# Sensor.net
KiCad netlist of a schematic drawn in Altium Designer
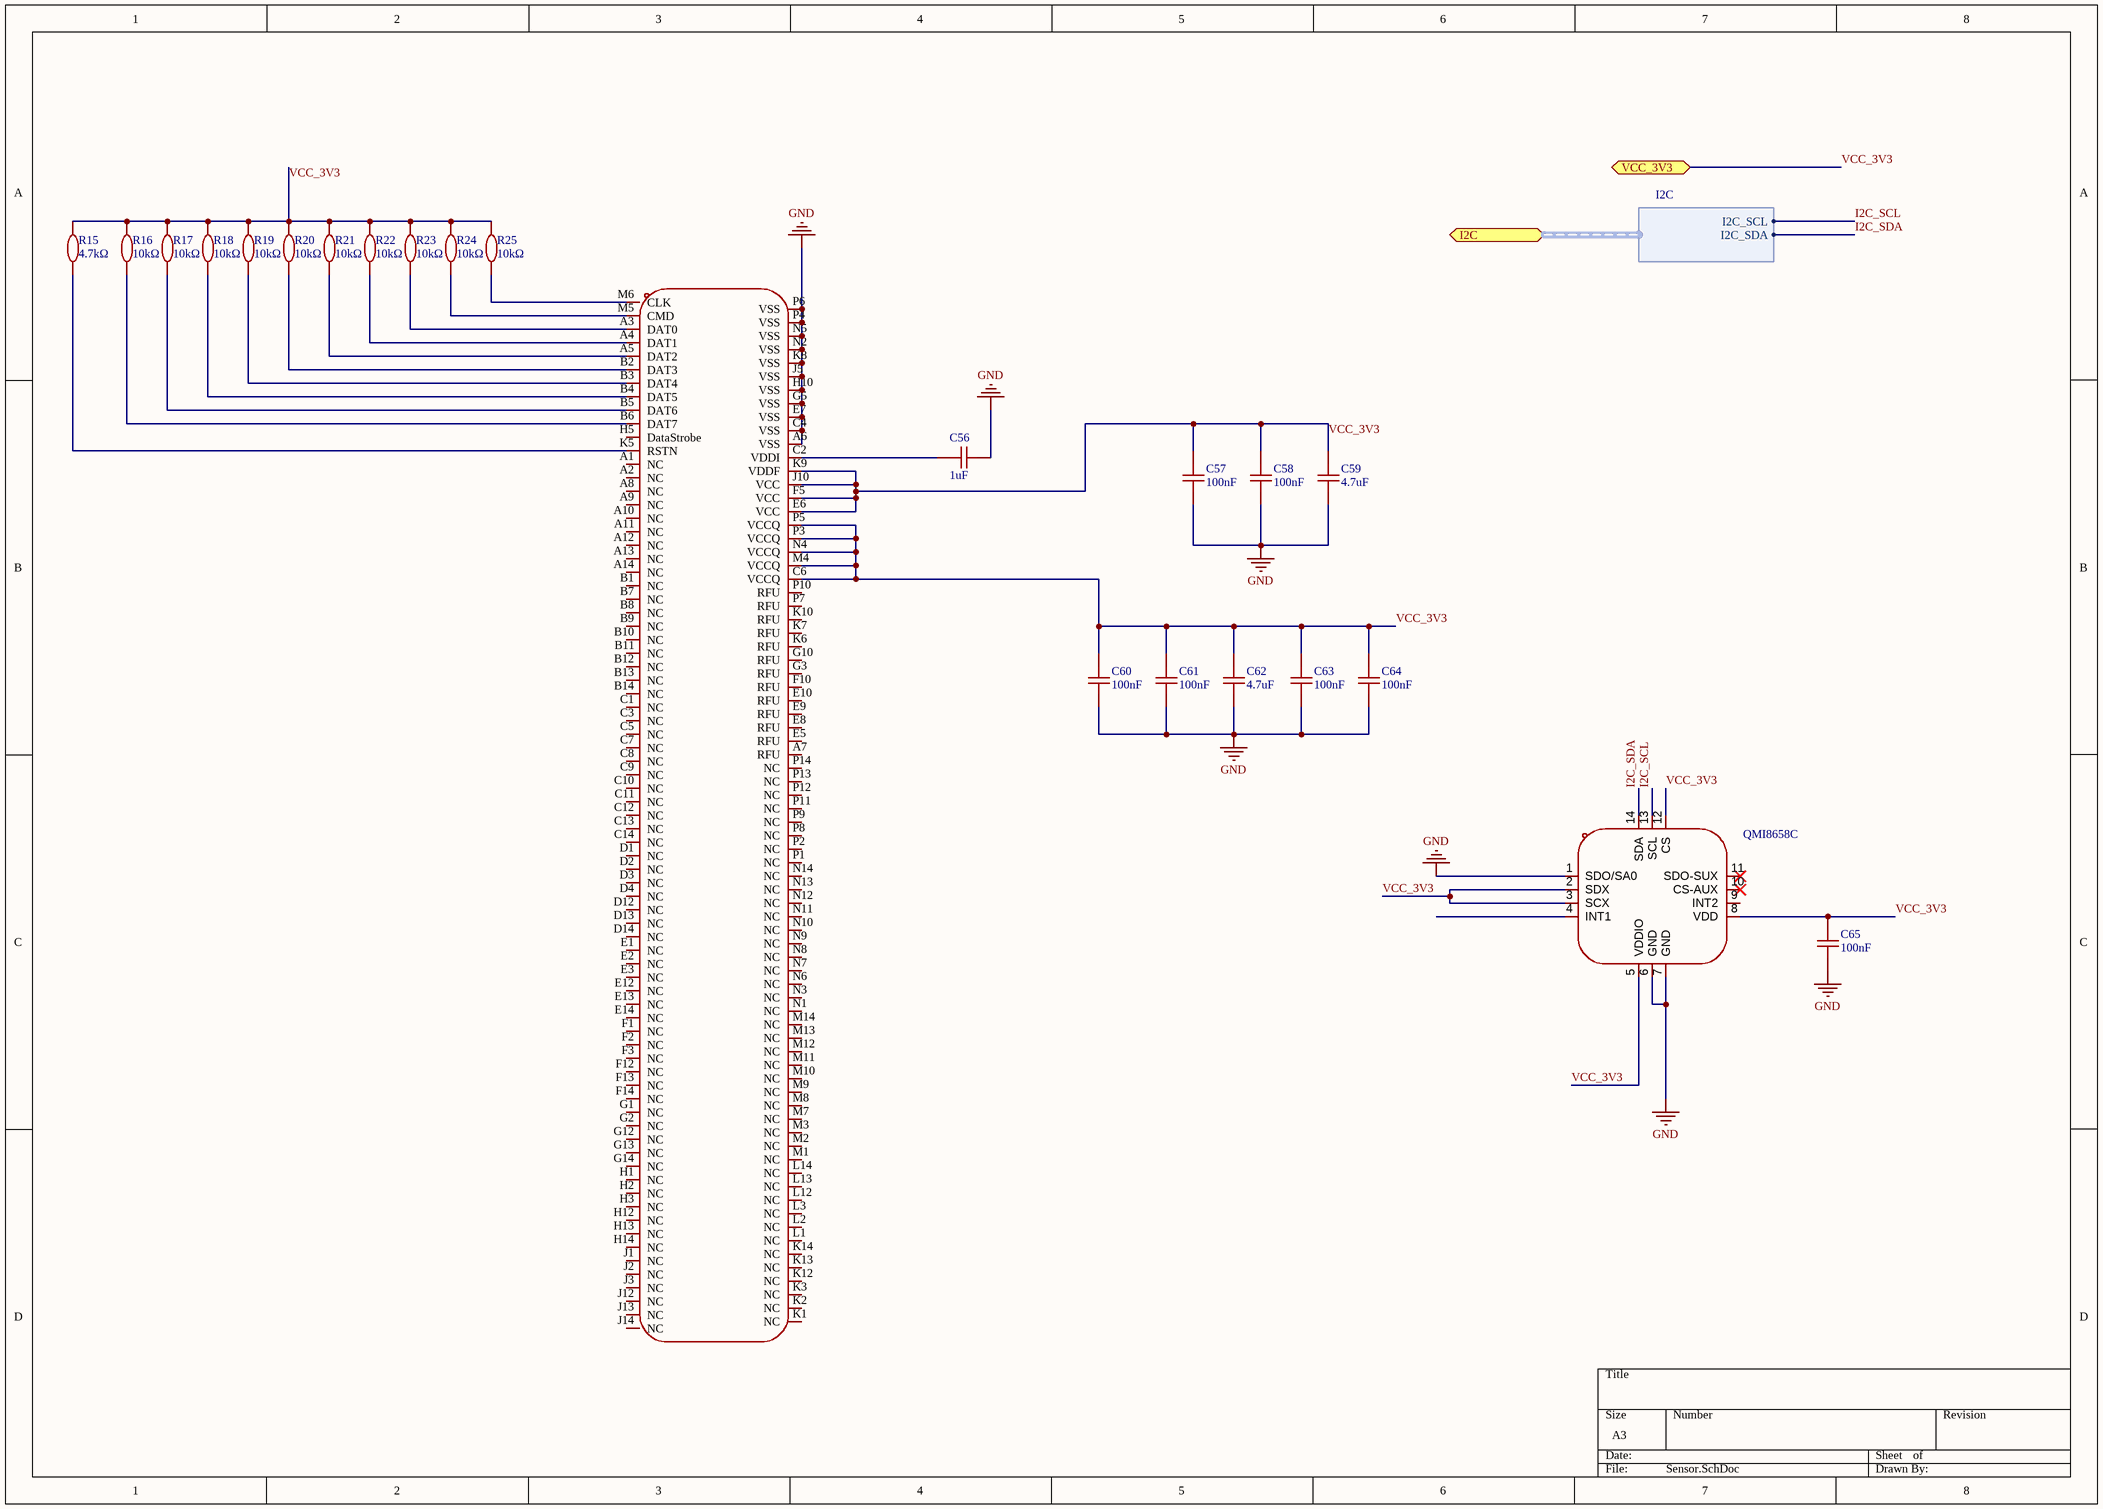
[diagram p0: Sensor.SchDoc]

(export (version "E")
  (design (tool "Eeschema 10.0.6"))
  (components
    (comp (ref "C56")
      (value "1uF")
      (footprint "C0402")
      (description "50V 1uF X5R ±10% 0402 Ceramic Capacitors ROHS")
      (libsource (lib "RLC") (part "1uF"))
    )
    (comp (ref "C57")
      (value "100nF")
      (footprint "C0402")
      (description "50V 100nF X7R ±10% 0402 Ceramic Capacitors ROHS")
      (libsource (lib "RLC") (part "100nF"))
    )
    (comp (ref "C58")
      (value "100nF")
      (footprint "C0402")
      (description "50V 100nF X7R ±10% 0402 Ceramic Capacitors ROHS")
      (libsource (lib "RLC") (part "100nF"))
    )
    (comp (ref "C59")
      (value "4.7uF")
      (footprint "C0402")
      (description "10V 4.7uF X5R ±20% 0402 Ceramic Capacitors ROHS")
      (libsource (lib "RLC") (part "4.7uF"))
    )
    (comp (ref "C60")
      (value "100nF")
      (footprint "C0402")
      (description "50V 100nF X7R ±10% 0402 Ceramic Capacitors ROHS")
      (libsource (lib "RLC") (part "100nF"))
    )
    (comp (ref "C61")
      (value "100nF")
      (footprint "C0402")
      (description "50V 100nF X7R ±10% 0402 Ceramic Capacitors ROHS")
      (libsource (lib "RLC") (part "100nF"))
    )
    (comp (ref "C62")
      (value "4.7uF")
      (footprint "C0402")
      (description "10V 4.7uF X5R ±20% 0402 Ceramic Capacitors ROHS")
      (libsource (lib "RLC") (part "4.7uF"))
    )
    (comp (ref "C63")
      (value "100nF")
      (footprint "C0402")
      (description "50V 100nF X7R ±10% 0402 Ceramic Capacitors ROHS")
      (libsource (lib "RLC") (part "100nF"))
    )
    (comp (ref "C64")
      (value "100nF")
      (footprint "C0402")
      (description "50V 100nF X7R ±10% 0402 Ceramic Capacitors ROHS")
      (libsource (lib "RLC") (part "100nF"))
    )
    (comp (ref "C65")
      (value "100nF")
      (footprint "C0402")
      (description "50V 100nF X7R ±10% 0402 Ceramic Capacitors ROHS")
      (libsource (lib "RLC") (part "100nF"))
    )
    (comp (ref "R15")
      (value "4.7kΩ")
      (footprint "R0402")
      (description "62.5mW 10kΩ 50V ±100ppm/℃ Thick Film Resistor ±1% 0402 Chip Resistor - Surface Mount ROHS")
      (libsource (lib "RLC") (part "10kΩ"))
    )
    (comp (ref "R16")
      (value "10kΩ")
      (footprint "R0402")
      (description "62.5mW 10kΩ 50V ±100ppm/℃ Thick Film Resistor ±1% 0402 Chip Resistor - Surface Mount ROHS")
      (libsource (lib "RLC") (part "10kΩ"))
    )
    (comp (ref "R17")
      (value "10kΩ")
      (footprint "R0402")
      (description "62.5mW 10kΩ 50V ±100ppm/℃ Thick Film Resistor ±1% 0402 Chip Resistor - Surface Mount ROHS")
      (libsource (lib "RLC") (part "10kΩ"))
    )
    (comp (ref "R18")
      (value "10kΩ")
      (footprint "R0402")
      (description "62.5mW 10kΩ 50V ±100ppm/℃ Thick Film Resistor ±1% 0402 Chip Resistor - Surface Mount ROHS")
      (libsource (lib "RLC") (part "10kΩ"))
    )
    (comp (ref "R19")
      (value "10kΩ")
      (footprint "R0402")
      (description "62.5mW 10kΩ 50V ±100ppm/℃ Thick Film Resistor ±1% 0402 Chip Resistor - Surface Mount ROHS")
      (libsource (lib "RLC") (part "10kΩ"))
    )
    (comp (ref "R20")
      (value "10kΩ")
      (footprint "R0402")
      (description "62.5mW 10kΩ 50V ±100ppm/℃ Thick Film Resistor ±1% 0402 Chip Resistor - Surface Mount ROHS")
      (libsource (lib "RLC") (part "10kΩ"))
    )
    (comp (ref "R21")
      (value "10kΩ")
      (footprint "R0402")
      (description "62.5mW 10kΩ 50V ±100ppm/℃ Thick Film Resistor ±1% 0402 Chip Resistor - Surface Mount ROHS")
      (libsource (lib "RLC") (part "10kΩ"))
    )
    (comp (ref "R22")
      (value "10kΩ")
      (footprint "R0402")
      (description "62.5mW 10kΩ 50V ±100ppm/℃ Thick Film Resistor ±1% 0402 Chip Resistor - Surface Mount ROHS")
      (libsource (lib "RLC") (part "10kΩ"))
    )
    (comp (ref "R23")
      (value "10kΩ")
      (footprint "R0402")
      (description "62.5mW 10kΩ 50V ±100ppm/℃ Thick Film Resistor ±1% 0402 Chip Resistor - Surface Mount ROHS")
      (libsource (lib "RLC") (part "10kΩ"))
    )
    (comp (ref "R24")
      (value "10kΩ")
      (footprint "R0402")
      (description "62.5mW 10kΩ 50V ±100ppm/℃ Thick Film Resistor ±1% 0402 Chip Resistor - Surface Mount ROHS")
      (libsource (lib "RLC") (part "10kΩ"))
    )
    (comp (ref "R25")
      (value "10kΩ")
      (footprint "R0402")
      (description "62.5mW 10kΩ 50V ±100ppm/℃ Thick Film Resistor ±1% 0402 Chip Resistor - Surface Mount ROHS")
      (libsource (lib "RLC") (part "10kΩ"))
    )
    (comp (ref "U10")
      (value "QMI8658C")
      (footprint "LGA-14_L3.0-W2.5-P0.50-BR")
      (description "低噪声、宽带宽6D惯性测量单元，带运动协处理器和传感器融合功能")
      (libsource (lib "IC") (part "QMI8658C"))
    )
    (comp (ref "U11")
      (value "KLM8G1GETF-B041")
      (footprint "FBGA-153_L13.0-W11.5-P0.50_KLMAG1JETD-B041")
      (description "8GB 2.7V~3.6V eMMC 5.1 330/50 MB/s FBGA-153(11.5x13) Memory (ICs) ROHS")
      (fields (field (name "MANUFACTURER") "SAMSUNG(三星半导体)"))
      (libsource (lib "IC") (part "KLM8G1GETF-B041_1"))
    )
  )
  (nets
    (net (code "2") (name "/I2C_SCL") (class "Default")
      (node (ref "U10") (pin "13") (pinfunction "SCL_13") (pintype "passive"))
    )
    (net (code "3") (name "/I2C_SDA") (class "Default")
      (node (ref "U10") (pin "14") (pinfunction "SDA_14") (pintype "passive"))
    )
    (net (code "4") (name "/VCC_3V3") (class "Default")
      (node (ref "C57") (pin "2") (pinfunction "2_2") (pintype "passive"))
      (node (ref "C58") (pin "2") (pinfunction "2_2") (pintype "passive"))
      (node (ref "C59") (pin "2") (pinfunction "2_2") (pintype "passive"))
      (node (ref "C60") (pin "2") (pinfunction "2_2") (pintype "passive"))
      (node (ref "C61") (pin "2") (pinfunction "2_2") (pintype "passive"))
      (node (ref "C62") (pin "2") (pinfunction "2_2") (pintype "passive"))
      (node (ref "C63") (pin "2") (pinfunction "2_2") (pintype "passive"))
      (node (ref "C64") (pin "2") (pinfunction "2_2") (pintype "passive"))
      (node (ref "C65") (pin "2") (pinfunction "2_2") (pintype "passive"))
      (node (ref "R15") (pin "2") (pinfunction "2_2") (pintype "passive"))
      (node (ref "R16") (pin "2") (pinfunction "2_2") (pintype "passive"))
      (node (ref "R17") (pin "2") (pinfunction "2_2") (pintype "passive"))
      (node (ref "R18") (pin "2") (pinfunction "2_2") (pintype "passive"))
      (node (ref "R19") (pin "2") (pinfunction "2_2") (pintype "passive"))
      (node (ref "R20") (pin "2") (pinfunction "2_2") (pintype "passive"))
      (node (ref "R21") (pin "2") (pinfunction "2_2") (pintype "passive"))
      (node (ref "R22") (pin "2") (pinfunction "2_2") (pintype "passive"))
      (node (ref "R23") (pin "2") (pinfunction "2_2") (pintype "passive"))
      (node (ref "R24") (pin "2") (pinfunction "2_2") (pintype "passive"))
      (node (ref "R25") (pin "2") (pinfunction "2_2") (pintype "passive"))
      (node (ref "U10") (pin "12") (pinfunction "CS_12") (pintype "passive"))
      (node (ref "U10") (pin "2") (pinfunction "SDX_2") (pintype "passive"))
      (node (ref "U10") (pin "3") (pinfunction "SCX_3") (pintype "passive"))
      (node (ref "U10") (pin "5") (pinfunction "VDDIO_5") (pintype "passive"))
      (node (ref "U10") (pin "8") (pinfunction "VDD_8") (pintype "passive"))
      (node (ref "U11") (pin "C6") (pinfunction "VCCQ_C6") (pintype "passive"))
      (node (ref "U11") (pin "E6") (pinfunction "VCC_E6") (pintype "passive"))
      (node (ref "U11") (pin "F5") (pinfunction "VCC_F5") (pintype "passive"))
      (node (ref "U11") (pin "J10") (pinfunction "VCC_J10") (pintype "passive"))
      (node (ref "U11") (pin "K9") (pinfunction "VDDF_K9") (pintype "passive"))
      (node (ref "U11") (pin "M4") (pinfunction "VCCQ_M4") (pintype "passive"))
      (node (ref "U11") (pin "N4") (pinfunction "VCCQ_N4") (pintype "passive"))
      (node (ref "U11") (pin "P3") (pinfunction "VCCQ_P3") (pintype "passive"))
      (node (ref "U11") (pin "P5") (pinfunction "VCCQ_P5") (pintype "passive"))
    )
    (net (code "6") (name "GND") (class "Default")
      (node (ref "C56") (pin "2") (pinfunction "2_2") (pintype "passive"))
      (node (ref "C57") (pin "1") (pinfunction "1_1") (pintype "passive"))
      (node (ref "C58") (pin "1") (pinfunction "1_1") (pintype "passive"))
      (node (ref "C59") (pin "1") (pinfunction "1_1") (pintype "passive"))
      (node (ref "C60") (pin "1") (pinfunction "1_1") (pintype "passive"))
      (node (ref "C61") (pin "1") (pinfunction "1_1") (pintype "passive"))
      (node (ref "C62") (pin "1") (pinfunction "1_1") (pintype "passive"))
      (node (ref "C63") (pin "1") (pinfunction "1_1") (pintype "passive"))
      (node (ref "C64") (pin "1") (pinfunction "1_1") (pintype "passive"))
      (node (ref "C65") (pin "1") (pinfunction "1_1") (pintype "passive"))
      (node (ref "U10") (pin "1") (pinfunction "SDO/SA0_1") (pintype "passive"))
      (node (ref "U10") (pin "6") (pinfunction "GND_6") (pintype "passive"))
      (node (ref "U10") (pin "7") (pinfunction "GND_7") (pintype "passive"))
      (node (ref "U11") (pin "A6") (pinfunction "VSS_A6") (pintype "passive"))
      (node (ref "U11") (pin "C4") (pinfunction "VSS_C4") (pintype "passive"))
      (node (ref "U11") (pin "E7") (pinfunction "VSS_E7") (pintype "passive"))
      (node (ref "U11") (pin "G5") (pinfunction "VSS_G5") (pintype "passive"))
      (node (ref "U11") (pin "H10") (pinfunction "VSS_H10") (pintype "passive"))
      (node (ref "U11") (pin "J5") (pinfunction "VSS_J5") (pintype "passive"))
      (node (ref "U11") (pin "K8") (pinfunction "VSS_K8") (pintype "passive"))
      (node (ref "U11") (pin "N2") (pinfunction "VSS_N2") (pintype "passive"))
      (node (ref "U11") (pin "N5") (pinfunction "VSS_N5") (pintype "passive"))
      (node (ref "U11") (pin "P4") (pinfunction "VSS_P4") (pintype "passive"))
      (node (ref "U11") (pin "P6") (pinfunction "VSS_P6") (pintype "passive"))
    )
    (net (code "7") (name "Net-(U11-CLK)") (class "Default")
      (node (ref "R25") (pin "1") (pinfunction "1_1") (pintype "passive"))
      (node (ref "U11") (pin "M6") (pinfunction "CLK_M6") (pintype "passive"))
    )
    (net (code "8") (name "Net-(U11-CMD)") (class "Default")
      (node (ref "R24") (pin "1") (pinfunction "1_1") (pintype "passive"))
      (node (ref "U11") (pin "M5") (pinfunction "CMD_M5") (pintype "passive"))
    )
    (net (code "9") (name "Net-(U11-DAT0)") (class "Default")
      (node (ref "R23") (pin "1") (pinfunction "1_1") (pintype "passive"))
      (node (ref "U11") (pin "A3") (pinfunction "DAT0_A3") (pintype "passive"))
    )
    (net (code "10") (name "Net-(U11-DAT1)") (class "Default")
      (node (ref "R22") (pin "1") (pinfunction "1_1") (pintype "passive"))
      (node (ref "U11") (pin "A4") (pinfunction "DAT1_A4") (pintype "passive"))
    )
    (net (code "11") (name "Net-(U11-DAT2)") (class "Default")
      (node (ref "R21") (pin "1") (pinfunction "1_1") (pintype "passive"))
      (node (ref "U11") (pin "A5") (pinfunction "DAT2_A5") (pintype "passive"))
    )
    (net (code "12") (name "Net-(U11-DAT3)") (class "Default")
      (node (ref "R20") (pin "1") (pinfunction "1_1") (pintype "passive"))
      (node (ref "U11") (pin "B2") (pinfunction "DAT3_B2") (pintype "passive"))
    )
    (net (code "13") (name "Net-(U11-DAT4)") (class "Default")
      (node (ref "R19") (pin "1") (pinfunction "1_1") (pintype "passive"))
      (node (ref "U11") (pin "B3") (pinfunction "DAT4_B3") (pintype "passive"))
    )
    (net (code "14") (name "Net-(U11-DAT5)") (class "Default")
      (node (ref "R18") (pin "1") (pinfunction "1_1") (pintype "passive"))
      (node (ref "U11") (pin "B4") (pinfunction "DAT5_B4") (pintype "passive"))
    )
    (net (code "15") (name "Net-(U11-DAT6)") (class "Default")
      (node (ref "R17") (pin "1") (pinfunction "1_1") (pintype "passive"))
      (node (ref "U11") (pin "B5") (pinfunction "DAT6_B5") (pintype "passive"))
    )
    (net (code "16") (name "Net-(U11-DAT7)") (class "Default")
      (node (ref "R16") (pin "1") (pinfunction "1_1") (pintype "passive"))
      (node (ref "U11") (pin "B6") (pinfunction "DAT7_B6") (pintype "passive"))
    )
    (net (code "17") (name "Net-(U11-RSTN)") (class "Default")
      (node (ref "R15") (pin "1") (pinfunction "1_1") (pintype "passive"))
      (node (ref "U11") (pin "K5") (pinfunction "RSTN_K5") (pintype "passive"))
    )
    (net (code "18") (name "Net-(U11-VDDI)") (class "Default")
      (node (ref "C56") (pin "1") (pinfunction "1_1") (pintype "passive"))
      (node (ref "U11") (pin "C2") (pinfunction "VDDI_C2") (pintype "passive"))
    )
    (net (code "19") (name "unconnected-(U10-CS-AUX-Pad10)") (class "Default")
      (node (ref "U10") (pin "10") (pinfunction "CS-AUX_10") (pintype "passive+no_connect"))
    )
    (net (code "20") (name "unconnected-(U10-INT1-Pad4)") (class "Default")
      (node (ref "U10") (pin "4") (pinfunction "INT1_4") (pintype "passive"))
    )
    (net (code "21") (name "unconnected-(U10-INT2-Pad9)") (class "Default")
      (node (ref "U10") (pin "9") (pinfunction "INT2_9") (pintype "passive"))
    )
    (net (code "22") (name "unconnected-(U10-SDO-SUX-Pad11)") (class "Default")
      (node (ref "U10") (pin "11") (pinfunction "SDO-SUX_11") (pintype "passive+no_connect"))
    )
    (net (code "23") (name "unconnected-(U11-DataStrobe-PadH5)") (class "Default")
      (node (ref "U11") (pin "H5") (pinfunction "DataStrobe_H5") (pintype "passive"))
    )
    (net (code "24") (name "unconnected-(U11-NC-PadA1)") (class "Default")
      (node (ref "U11") (pin "A1") (pinfunction "NC_A1") (pintype "passive"))
    )
    (net (code "25") (name "unconnected-(U11-NC-PadA2)") (class "Default")
      (node (ref "U11") (pin "A2") (pinfunction "NC_A2") (pintype "passive"))
    )
    (net (code "26") (name "unconnected-(U11-NC-PadA8)") (class "Default")
      (node (ref "U11") (pin "A8") (pinfunction "NC_A8") (pintype "passive"))
    )
    (net (code "27") (name "unconnected-(U11-NC-PadA9)") (class "Default")
      (node (ref "U11") (pin "A9") (pinfunction "NC_A9") (pintype "passive"))
    )
    (net (code "28") (name "unconnected-(U11-NC-PadA10)") (class "Default")
      (node (ref "U11") (pin "A10") (pinfunction "NC_A10") (pintype "passive"))
    )
    (net (code "29") (name "unconnected-(U11-NC-PadA11)") (class "Default")
      (node (ref "U11") (pin "A11") (pinfunction "NC_A11") (pintype "passive"))
    )
    (net (code "30") (name "unconnected-(U11-NC-PadA12)") (class "Default")
      (node (ref "U11") (pin "A12") (pinfunction "NC_A12") (pintype "passive"))
    )
    (net (code "31") (name "unconnected-(U11-NC-PadA13)") (class "Default")
      (node (ref "U11") (pin "A13") (pinfunction "NC_A13") (pintype "passive"))
    )
    (net (code "32") (name "unconnected-(U11-NC-PadA14)") (class "Default")
      (node (ref "U11") (pin "A14") (pinfunction "NC_A14") (pintype "passive"))
    )
    (net (code "33") (name "unconnected-(U11-NC-PadB1)") (class "Default")
      (node (ref "U11") (pin "B1") (pinfunction "NC_B1") (pintype "passive"))
    )
    (net (code "34") (name "unconnected-(U11-NC-PadB7)") (class "Default")
      (node (ref "U11") (pin "B7") (pinfunction "NC_B7") (pintype "passive"))
    )
    (net (code "35") (name "unconnected-(U11-NC-PadB8)") (class "Default")
      (node (ref "U11") (pin "B8") (pinfunction "NC_B8") (pintype "passive"))
    )
    (net (code "36") (name "unconnected-(U11-NC-PadB9)") (class "Default")
      (node (ref "U11") (pin "B9") (pinfunction "NC_B9") (pintype "passive"))
    )
    (net (code "37") (name "unconnected-(U11-NC-PadB10)") (class "Default")
      (node (ref "U11") (pin "B10") (pinfunction "NC_B10") (pintype "passive"))
    )
    (net (code "38") (name "unconnected-(U11-NC-PadB11)") (class "Default")
      (node (ref "U11") (pin "B11") (pinfunction "NC_B11") (pintype "passive"))
    )
    (net (code "39") (name "unconnected-(U11-NC-PadB12)") (class "Default")
      (node (ref "U11") (pin "B12") (pinfunction "NC_B12") (pintype "passive"))
    )
    (net (code "40") (name "unconnected-(U11-NC-PadB13)") (class "Default")
      (node (ref "U11") (pin "B13") (pinfunction "NC_B13") (pintype "passive"))
    )
    (net (code "41") (name "unconnected-(U11-NC-PadB14)") (class "Default")
      (node (ref "U11") (pin "B14") (pinfunction "NC_B14") (pintype "passive"))
    )
    (net (code "42") (name "unconnected-(U11-NC-PadC1)") (class "Default")
      (node (ref "U11") (pin "C1") (pinfunction "NC_C1") (pintype "passive"))
    )
    (net (code "43") (name "unconnected-(U11-NC-PadC3)") (class "Default")
      (node (ref "U11") (pin "C3") (pinfunction "NC_C3") (pintype "passive"))
    )
    (net (code "44") (name "unconnected-(U11-NC-PadC5)") (class "Default")
      (node (ref "U11") (pin "C5") (pinfunction "NC_C5") (pintype "passive"))
    )
    (net (code "45") (name "unconnected-(U11-NC-PadC7)") (class "Default")
      (node (ref "U11") (pin "C7") (pinfunction "NC_C7") (pintype "passive"))
    )
    (net (code "46") (name "unconnected-(U11-NC-PadC8)") (class "Default")
      (node (ref "U11") (pin "C8") (pinfunction "NC_C8") (pintype "passive"))
    )
    (net (code "47") (name "unconnected-(U11-NC-PadC9)") (class "Default")
      (node (ref "U11") (pin "C9") (pinfunction "NC_C9") (pintype "passive"))
    )
    (net (code "48") (name "unconnected-(U11-NC-PadC10)") (class "Default")
      (node (ref "U11") (pin "C10") (pinfunction "NC_C10") (pintype "passive"))
    )
    (net (code "49") (name "unconnected-(U11-NC-PadC11)") (class "Default")
      (node (ref "U11") (pin "C11") (pinfunction "NC_C11") (pintype "passive"))
    )
    (net (code "50") (name "unconnected-(U11-NC-PadC12)") (class "Default")
      (node (ref "U11") (pin "C12") (pinfunction "NC_C12") (pintype "passive"))
    )
    (net (code "51") (name "unconnected-(U11-NC-PadC13)") (class "Default")
      (node (ref "U11") (pin "C13") (pinfunction "NC_C13") (pintype "passive"))
    )
    (net (code "52") (name "unconnected-(U11-NC-PadC14)") (class "Default")
      (node (ref "U11") (pin "C14") (pinfunction "NC_C14") (pintype "passive"))
    )
    (net (code "53") (name "unconnected-(U11-NC-PadD1)") (class "Default")
      (node (ref "U11") (pin "D1") (pinfunction "NC_D1") (pintype "passive"))
    )
    (net (code "54") (name "unconnected-(U11-NC-PadD2)") (class "Default")
      (node (ref "U11") (pin "D2") (pinfunction "NC_D2") (pintype "passive"))
    )
    (net (code "55") (name "unconnected-(U11-NC-PadD3)") (class "Default")
      (node (ref "U11") (pin "D3") (pinfunction "NC_D3") (pintype "passive"))
    )
    (net (code "56") (name "unconnected-(U11-NC-PadD4)") (class "Default")
      (node (ref "U11") (pin "D4") (pinfunction "NC_D4") (pintype "passive"))
    )
    (net (code "57") (name "unconnected-(U11-NC-PadD12)") (class "Default")
      (node (ref "U11") (pin "D12") (pinfunction "NC_D12") (pintype "passive"))
    )
    (net (code "58") (name "unconnected-(U11-NC-PadD13)") (class "Default")
      (node (ref "U11") (pin "D13") (pinfunction "NC_D13") (pintype "passive"))
    )
    (net (code "59") (name "unconnected-(U11-NC-PadD14)") (class "Default")
      (node (ref "U11") (pin "D14") (pinfunction "NC_D14") (pintype "passive"))
    )
    (net (code "60") (name "unconnected-(U11-NC-PadE1)") (class "Default")
      (node (ref "U11") (pin "E1") (pinfunction "NC_E1") (pintype "passive"))
    )
    (net (code "61") (name "unconnected-(U11-NC-PadE2)") (class "Default")
      (node (ref "U11") (pin "E2") (pinfunction "NC_E2") (pintype "passive"))
    )
    (net (code "62") (name "unconnected-(U11-NC-PadE3)") (class "Default")
      (node (ref "U11") (pin "E3") (pinfunction "NC_E3") (pintype "passive"))
    )
    (net (code "63") (name "unconnected-(U11-NC-PadE12)") (class "Default")
      (node (ref "U11") (pin "E12") (pinfunction "NC_E12") (pintype "passive"))
    )
    (net (code "64") (name "unconnected-(U11-NC-PadE13)") (class "Default")
      (node (ref "U11") (pin "E13") (pinfunction "NC_E13") (pintype "passive"))
    )
    (net (code "65") (name "unconnected-(U11-NC-PadE14)") (class "Default")
      (node (ref "U11") (pin "E14") (pinfunction "NC_E14") (pintype "passive"))
    )
    (net (code "66") (name "unconnected-(U11-NC-PadF1)") (class "Default")
      (node (ref "U11") (pin "F1") (pinfunction "NC_F1") (pintype "passive"))
    )
    (net (code "67") (name "unconnected-(U11-NC-PadF2)") (class "Default")
      (node (ref "U11") (pin "F2") (pinfunction "NC_F2") (pintype "passive"))
    )
    (net (code "68") (name "unconnected-(U11-NC-PadF3)") (class "Default")
      (node (ref "U11") (pin "F3") (pinfunction "NC_F3") (pintype "passive"))
    )
    (net (code "69") (name "unconnected-(U11-NC-PadF12)") (class "Default")
      (node (ref "U11") (pin "F12") (pinfunction "NC_F12") (pintype "passive"))
    )
    (net (code "70") (name "unconnected-(U11-NC-PadF13)") (class "Default")
      (node (ref "U11") (pin "F13") (pinfunction "NC_F13") (pintype "passive"))
    )
    (net (code "71") (name "unconnected-(U11-NC-PadF14)") (class "Default")
      (node (ref "U11") (pin "F14") (pinfunction "NC_F14") (pintype "passive"))
    )
    (net (code "72") (name "unconnected-(U11-NC-PadG1)") (class "Default")
      (node (ref "U11") (pin "G1") (pinfunction "NC_G1") (pintype "passive"))
    )
    (net (code "73") (name "unconnected-(U11-NC-PadG2)") (class "Default")
      (node (ref "U11") (pin "G2") (pinfunction "NC_G2") (pintype "passive"))
    )
    (net (code "74") (name "unconnected-(U11-NC-PadG12)") (class "Default")
      (node (ref "U11") (pin "G12") (pinfunction "NC_G12") (pintype "passive"))
    )
    (net (code "75") (name "unconnected-(U11-NC-PadG13)") (class "Default")
      (node (ref "U11") (pin "G13") (pinfunction "NC_G13") (pintype "passive"))
    )
    (net (code "76") (name "unconnected-(U11-NC-PadG14)") (class "Default")
      (node (ref "U11") (pin "G14") (pinfunction "NC_G14") (pintype "passive"))
    )
    (net (code "77") (name "unconnected-(U11-NC-PadH1)") (class "Default")
      (node (ref "U11") (pin "H1") (pinfunction "NC_H1") (pintype "passive"))
    )
    (net (code "78") (name "unconnected-(U11-NC-PadH2)") (class "Default")
      (node (ref "U11") (pin "H2") (pinfunction "NC_H2") (pintype "passive"))
    )
    (net (code "79") (name "unconnected-(U11-NC-PadH3)") (class "Default")
      (node (ref "U11") (pin "H3") (pinfunction "NC_H3") (pintype "passive"))
    )
    (net (code "80") (name "unconnected-(U11-NC-PadH12)") (class "Default")
      (node (ref "U11") (pin "H12") (pinfunction "NC_H12") (pintype "passive"))
    )
    (net (code "81") (name "unconnected-(U11-NC-PadH13)") (class "Default")
      (node (ref "U11") (pin "H13") (pinfunction "NC_H13") (pintype "passive"))
    )
    (net (code "82") (name "unconnected-(U11-NC-PadH14)") (class "Default")
      (node (ref "U11") (pin "H14") (pinfunction "NC_H14") (pintype "passive"))
    )
    (net (code "83") (name "unconnected-(U11-NC-PadJ1)") (class "Default")
      (node (ref "U11") (pin "J1") (pinfunction "NC_J1") (pintype "passive"))
    )
    (net (code "84") (name "unconnected-(U11-NC-PadJ2)") (class "Default")
      (node (ref "U11") (pin "J2") (pinfunction "NC_J2") (pintype "passive"))
    )
    (net (code "85") (name "unconnected-(U11-NC-PadJ3)") (class "Default")
      (node (ref "U11") (pin "J3") (pinfunction "NC_J3") (pintype "passive"))
    )
    (net (code "86") (name "unconnected-(U11-NC-PadJ12)") (class "Default")
      (node (ref "U11") (pin "J12") (pinfunction "NC_J12") (pintype "passive"))
    )
    (net (code "87") (name "unconnected-(U11-NC-PadJ13)") (class "Default")
      (node (ref "U11") (pin "J13") (pinfunction "NC_J13") (pintype "passive"))
    )
    (net (code "88") (name "unconnected-(U11-NC-PadJ14)") (class "Default")
      (node (ref "U11") (pin "J14") (pinfunction "NC_J14") (pintype "passive"))
    )
    (net (code "89") (name "unconnected-(U11-NC-PadK1)") (class "Default")
      (node (ref "U11") (pin "K1") (pinfunction "NC_K1") (pintype "passive"))
    )
    (net (code "90") (name "unconnected-(U11-NC-PadK2)") (class "Default")
      (node (ref "U11") (pin "K2") (pinfunction "NC_K2") (pintype "passive"))
    )
    (net (code "91") (name "unconnected-(U11-NC-PadK3)") (class "Default")
      (node (ref "U11") (pin "K3") (pinfunction "NC_K3") (pintype "passive"))
    )
    (net (code "92") (name "unconnected-(U11-NC-PadK12)") (class "Default")
      (node (ref "U11") (pin "K12") (pinfunction "NC_K12") (pintype "passive"))
    )
    (net (code "93") (name "unconnected-(U11-NC-PadK13)") (class "Default")
      (node (ref "U11") (pin "K13") (pinfunction "NC_K13") (pintype "passive"))
    )
    (net (code "94") (name "unconnected-(U11-NC-PadK14)") (class "Default")
      (node (ref "U11") (pin "K14") (pinfunction "NC_K14") (pintype "passive"))
    )
    (net (code "95") (name "unconnected-(U11-NC-PadL1)") (class "Default")
      (node (ref "U11") (pin "L1") (pinfunction "NC_L1") (pintype "passive"))
    )
    (net (code "96") (name "unconnected-(U11-NC-PadL2)") (class "Default")
      (node (ref "U11") (pin "L2") (pinfunction "NC_L2") (pintype "passive"))
    )
    (net (code "97") (name "unconnected-(U11-NC-PadL3)") (class "Default")
      (node (ref "U11") (pin "L3") (pinfunction "NC_L3") (pintype "passive"))
    )
    (net (code "98") (name "unconnected-(U11-NC-PadL12)") (class "Default")
      (node (ref "U11") (pin "L12") (pinfunction "NC_L12") (pintype "passive"))
    )
    (net (code "99") (name "unconnected-(U11-NC-PadL13)") (class "Default")
      (node (ref "U11") (pin "L13") (pinfunction "NC_L13") (pintype "passive"))
    )
    (net (code "100") (name "unconnected-(U11-NC-PadL14)") (class "Default")
      (node (ref "U11") (pin "L14") (pinfunction "NC_L14") (pintype "passive"))
    )
    (net (code "101") (name "unconnected-(U11-NC-PadM1)") (class "Default")
      (node (ref "U11") (pin "M1") (pinfunction "NC_M1") (pintype "passive"))
    )
    (net (code "102") (name "unconnected-(U11-NC-PadM2)") (class "Default")
      (node (ref "U11") (pin "M2") (pinfunction "NC_M2") (pintype "passive"))
    )
    (net (code "103") (name "unconnected-(U11-NC-PadM3)") (class "Default")
      (node (ref "U11") (pin "M3") (pinfunction "NC_M3") (pintype "passive"))
    )
    (net (code "104") (name "unconnected-(U11-NC-PadM7)") (class "Default")
      (node (ref "U11") (pin "M7") (pinfunction "NC_M7") (pintype "passive"))
    )
    (net (code "105") (name "unconnected-(U11-NC-PadM8)") (class "Default")
      (node (ref "U11") (pin "M8") (pinfunction "NC_M8") (pintype "passive"))
    )
    (net (code "106") (name "unconnected-(U11-NC-PadM9)") (class "Default")
      (node (ref "U11") (pin "M9") (pinfunction "NC_M9") (pintype "passive"))
    )
    (net (code "107") (name "unconnected-(U11-NC-PadM10)") (class "Default")
      (node (ref "U11") (pin "M10") (pinfunction "NC_M10") (pintype "passive"))
    )
    (net (code "108") (name "unconnected-(U11-NC-PadM11)") (class "Default")
      (node (ref "U11") (pin "M11") (pinfunction "NC_M11") (pintype "passive"))
    )
    (net (code "109") (name "unconnected-(U11-NC-PadM12)") (class "Default")
      (node (ref "U11") (pin "M12") (pinfunction "NC_M12") (pintype "passive"))
    )
    (net (code "110") (name "unconnected-(U11-NC-PadM13)") (class "Default")
      (node (ref "U11") (pin "M13") (pinfunction "NC_M13") (pintype "passive"))
    )
    (net (code "111") (name "unconnected-(U11-NC-PadM14)") (class "Default")
      (node (ref "U11") (pin "M14") (pinfunction "NC_M14") (pintype "passive"))
    )
    (net (code "112") (name "unconnected-(U11-NC-PadN1)") (class "Default")
      (node (ref "U11") (pin "N1") (pinfunction "NC_N1") (pintype "passive"))
    )
    (net (code "113") (name "unconnected-(U11-NC-PadN3)") (class "Default")
      (node (ref "U11") (pin "N3") (pinfunction "NC_N3") (pintype "passive"))
    )
    (net (code "114") (name "unconnected-(U11-NC-PadN6)") (class "Default")
      (node (ref "U11") (pin "N6") (pinfunction "NC_N6") (pintype "passive"))
    )
    (net (code "115") (name "unconnected-(U11-NC-PadN7)") (class "Default")
      (node (ref "U11") (pin "N7") (pinfunction "NC_N7") (pintype "passive"))
    )
    (net (code "116") (name "unconnected-(U11-NC-PadN8)") (class "Default")
      (node (ref "U11") (pin "N8") (pinfunction "NC_N8") (pintype "passive"))
    )
    (net (code "117") (name "unconnected-(U11-NC-PadN9)") (class "Default")
      (node (ref "U11") (pin "N9") (pinfunction "NC_N9") (pintype "passive"))
    )
    (net (code "118") (name "unconnected-(U11-NC-PadN10)") (class "Default")
      (node (ref "U11") (pin "N10") (pinfunction "NC_N10") (pintype "passive"))
    )
    (net (code "119") (name "unconnected-(U11-NC-PadN11)") (class "Default")
      (node (ref "U11") (pin "N11") (pinfunction "NC_N11") (pintype "passive"))
    )
    (net (code "120") (name "unconnected-(U11-NC-PadN12)") (class "Default")
      (node (ref "U11") (pin "N12") (pinfunction "NC_N12") (pintype "passive"))
    )
    (net (code "121") (name "unconnected-(U11-NC-PadN13)") (class "Default")
      (node (ref "U11") (pin "N13") (pinfunction "NC_N13") (pintype "passive"))
    )
    (net (code "122") (name "unconnected-(U11-NC-PadN14)") (class "Default")
      (node (ref "U11") (pin "N14") (pinfunction "NC_N14") (pintype "passive"))
    )
    (net (code "123") (name "unconnected-(U11-NC-PadP1)") (class "Default")
      (node (ref "U11") (pin "P1") (pinfunction "NC_P1") (pintype "passive"))
    )
    (net (code "124") (name "unconnected-(U11-NC-PadP2)") (class "Default")
      (node (ref "U11") (pin "P2") (pinfunction "NC_P2") (pintype "passive"))
    )
    (net (code "125") (name "unconnected-(U11-NC-PadP8)") (class "Default")
      (node (ref "U11") (pin "P8") (pinfunction "NC_P8") (pintype "passive"))
    )
    (net (code "126") (name "unconnected-(U11-NC-PadP9)") (class "Default")
      (node (ref "U11") (pin "P9") (pinfunction "NC_P9") (pintype "passive"))
    )
    (net (code "127") (name "unconnected-(U11-NC-PadP11)") (class "Default")
      (node (ref "U11") (pin "P11") (pinfunction "NC_P11") (pintype "passive"))
    )
    (net (code "128") (name "unconnected-(U11-NC-PadP12)") (class "Default")
      (node (ref "U11") (pin "P12") (pinfunction "NC_P12") (pintype "passive"))
    )
    (net (code "129") (name "unconnected-(U11-NC-PadP13)") (class "Default")
      (node (ref "U11") (pin "P13") (pinfunction "NC_P13") (pintype "passive"))
    )
    (net (code "130") (name "unconnected-(U11-NC-PadP14)") (class "Default")
      (node (ref "U11") (pin "P14") (pinfunction "NC_P14") (pintype "passive"))
    )
    (net (code "131") (name "unconnected-(U11-RFU-PadA7)") (class "Default")
      (node (ref "U11") (pin "A7") (pinfunction "RFU_A7") (pintype "passive"))
    )
    (net (code "132") (name "unconnected-(U11-RFU-PadE5)") (class "Default")
      (node (ref "U11") (pin "E5") (pinfunction "RFU_E5") (pintype "passive"))
    )
    (net (code "133") (name "unconnected-(U11-RFU-PadE8)") (class "Default")
      (node (ref "U11") (pin "E8") (pinfunction "RFU_E8") (pintype "passive"))
    )
    (net (code "134") (name "unconnected-(U11-RFU-PadE9)") (class "Default")
      (node (ref "U11") (pin "E9") (pinfunction "RFU_E9") (pintype "passive"))
    )
    (net (code "135") (name "unconnected-(U11-RFU-PadE10)") (class "Default")
      (node (ref "U11") (pin "E10") (pinfunction "RFU_E10") (pintype "passive"))
    )
    (net (code "136") (name "unconnected-(U11-RFU-PadF10)") (class "Default")
      (node (ref "U11") (pin "F10") (pinfunction "RFU_F10") (pintype "passive"))
    )
    (net (code "137") (name "unconnected-(U11-RFU-PadG3)") (class "Default")
      (node (ref "U11") (pin "G3") (pinfunction "RFU_G3") (pintype "passive"))
    )
    (net (code "138") (name "unconnected-(U11-RFU-PadG10)") (class "Default")
      (node (ref "U11") (pin "G10") (pinfunction "RFU_G10") (pintype "passive"))
    )
    (net (code "139") (name "unconnected-(U11-RFU-PadK6)") (class "Default")
      (node (ref "U11") (pin "K6") (pinfunction "RFU_K6") (pintype "passive"))
    )
    (net (code "140") (name "unconnected-(U11-RFU-PadK7)") (class "Default")
      (node (ref "U11") (pin "K7") (pinfunction "RFU_K7") (pintype "passive"))
    )
    (net (code "141") (name "unconnected-(U11-RFU-PadK10)") (class "Default")
      (node (ref "U11") (pin "K10") (pinfunction "RFU_K10") (pintype "passive"))
    )
    (net (code "142") (name "unconnected-(U11-RFU-PadP7)") (class "Default")
      (node (ref "U11") (pin "P7") (pinfunction "RFU_P7") (pintype "passive"))
    )
    (net (code "143") (name "unconnected-(U11-RFU-PadP10)") (class "Default")
      (node (ref "U11") (pin "P10") (pinfunction "RFU_P10") (pintype "passive"))
    )
  )
)
